# sx-wdec84-1_2.net
KiCad netlist of a schematic drawn in EAGLE
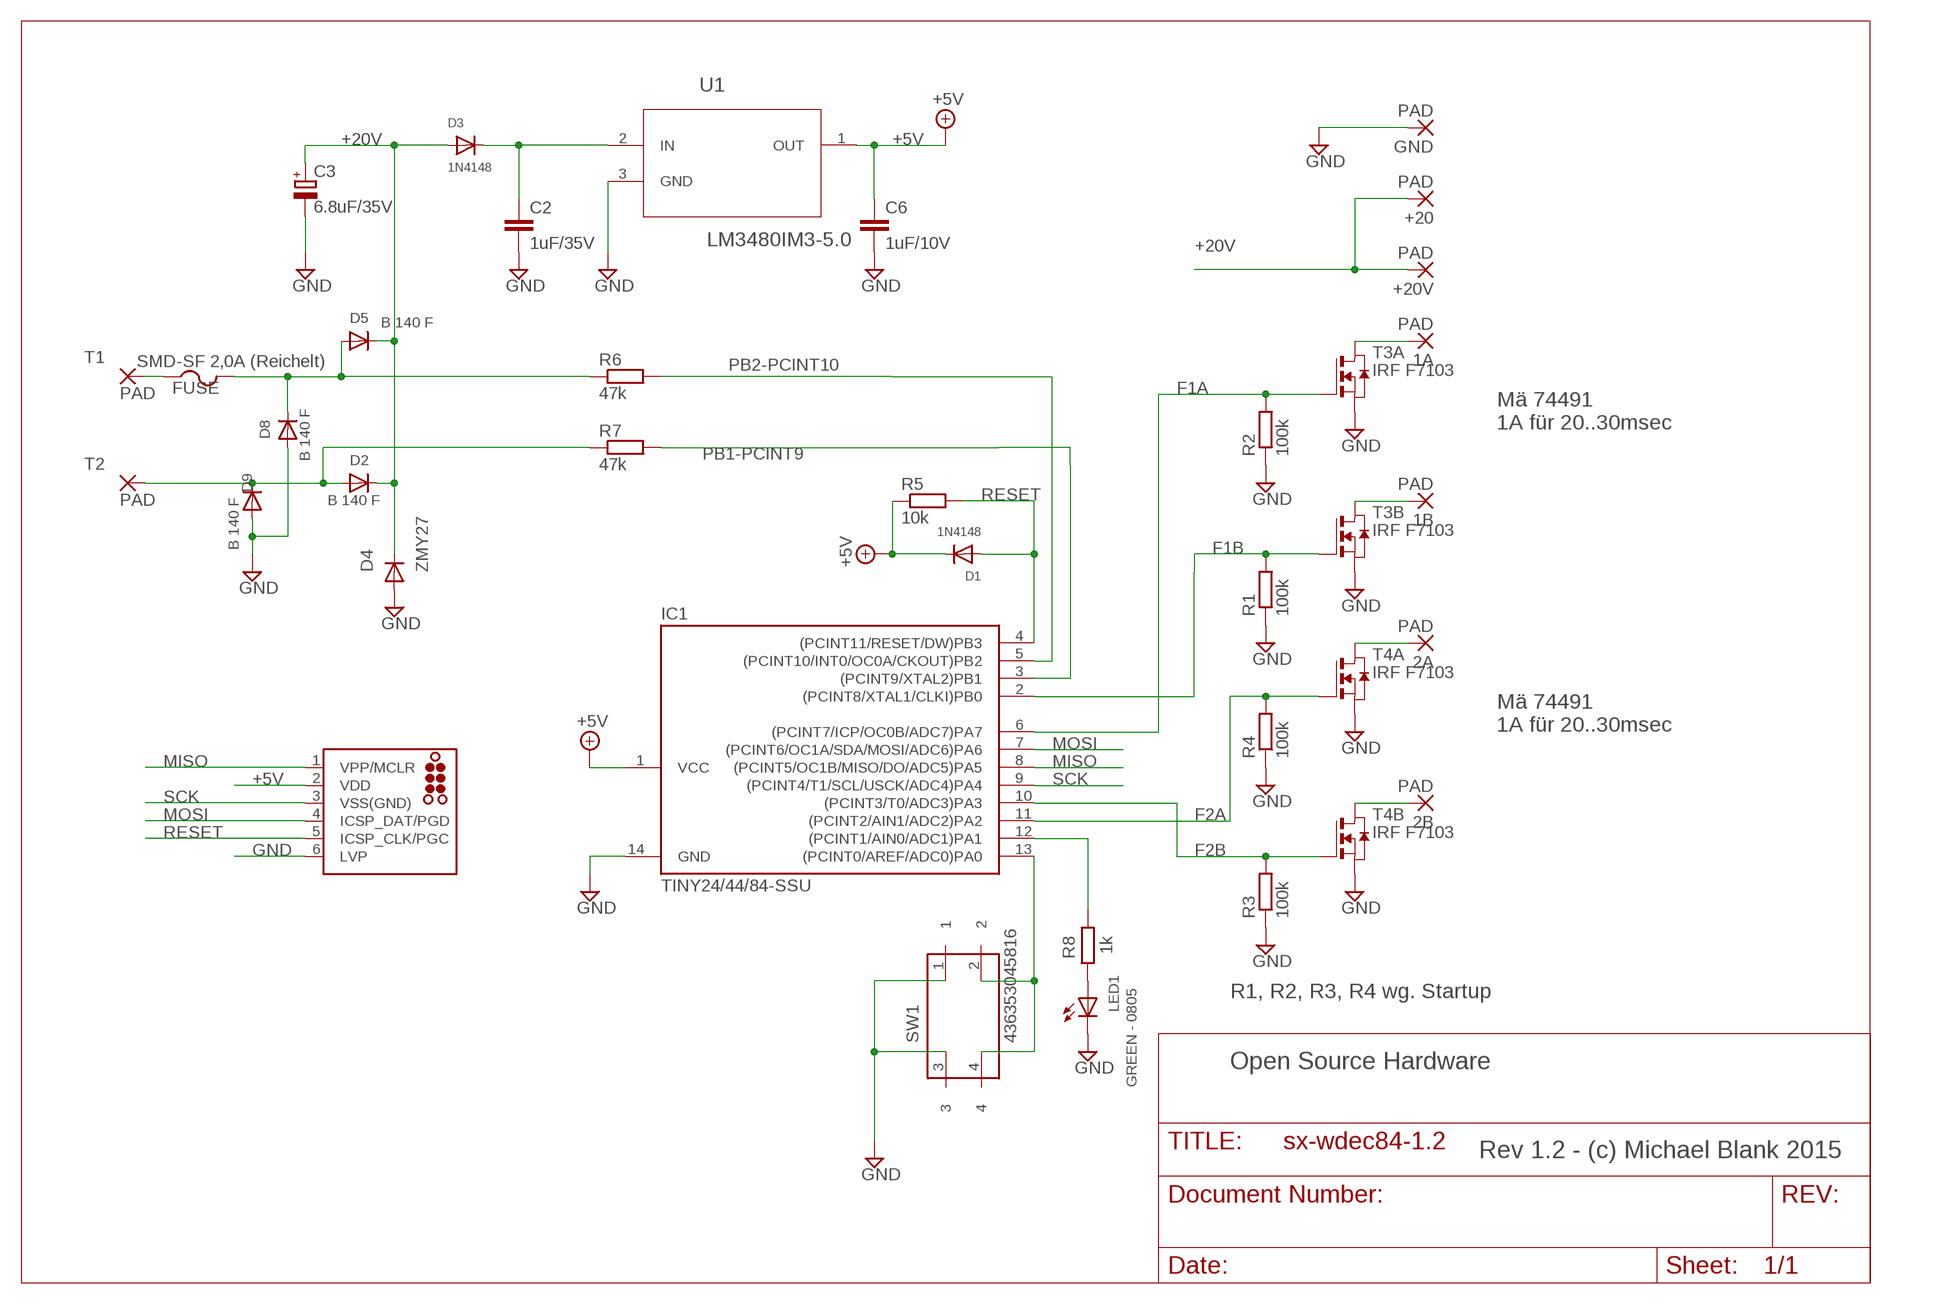
[diagram p0: schematic, sheet 1]

(export (version "E")
  (design (tool "Eeschema 10.0.6"))
  (components
    (comp (ref "+20")
      (value "PAD")
      (footprint "eagle-import:SMD1,27-2,54")
      (libsource (lib "eagle-import") (part "SMD2"))
    )
    (comp (ref "+20V")
      (value "PAD")
      (footprint "eagle-import:SMD1,27-2,54")
      (libsource (lib "eagle-import") (part "SMD2"))
    )
    (comp (ref "1A")
      (value "PAD")
      (footprint "eagle-import:SMD1,27-2,54")
      (libsource (lib "eagle-import") (part "SMD2"))
    )
    (comp (ref "1B")
      (value "PAD")
      (footprint "eagle-import:SMD1,27-2,54")
      (libsource (lib "eagle-import") (part "SMD2"))
    )
    (comp (ref "2A")
      (value "PAD")
      (footprint "eagle-import:SMD1,27-2,54")
      (libsource (lib "eagle-import") (part "SMD2"))
    )
    (comp (ref "2B")
      (value "PAD")
      (footprint "eagle-import:SMD1,27-2,54")
      (libsource (lib "eagle-import") (part "SMD2"))
    )
    (comp (ref "C2")
      (value "1uF/35V")
      (footprint "eagle-import:C0805")
      (libsource (lib "eagle-import") (part "C-EUC0805"))
    )
    (comp (ref "C3")
      (value "6.8uF/35V")
      (footprint "eagle-import:SMC_D")
      (libsource (lib "eagle-import") (part "CPOL-EUSMCD"))
    )
    (comp (ref "C6")
      (value "1uF/10V")
      (footprint "eagle-import:C0805")
      (libsource (lib "eagle-import") (part "C-EUC0805"))
    )
    (comp (ref "D1")
      (value "1N4148")
      (footprint "eagle-import:SOD-323F")
      (libsource (lib "eagle-import") (part "DIODESOD-323F"))
    )
    (comp (ref "D2")
      (value "B 140 F")
      (footprint "eagle-import:SMA-403D")
      (libsource (lib "eagle-import") (part "DIODESMA-403D"))
    )
    (comp (ref "D3")
      (value "1N4148")
      (footprint "eagle-import:SOD-323F")
      (libsource (lib "eagle-import") (part "DIODESOD-323F"))
    )
    (comp (ref "D4")
      (value "ZMY27")
      (footprint "eagle-import:MELF-MLL41")
      (libsource (lib "eagle-import") (part "DIODE-MELF-MLL41"))
    )
    (comp (ref "D5")
      (value "B 140 F")
      (footprint "eagle-import:SMA-403D")
      (libsource (lib "eagle-import") (part "DIODESMA-403D"))
    )
    (comp (ref "D8")
      (value "B 140 F")
      (footprint "eagle-import:SMA-403D")
      (libsource (lib "eagle-import") (part "DIODESMA-403D"))
    )
    (comp (ref "D9")
      (value "B 140 F")
      (footprint "eagle-import:SMA-403D")
      (libsource (lib "eagle-import") (part "DIODESMA-403D"))
    )
    (comp (ref "FUSE")
      (value "SMD-SF 2,0A (Reichelt)")
      (footprint "eagle-import:1812")
      (libsource (lib "eagle-import") (part "PTCFUSE-1812"))
    )
    (comp (ref "GND")
      (value "PAD")
      (footprint "eagle-import:SMD1,27-2,54")
      (libsource (lib "eagle-import") (part "SMD2"))
    )
    (comp (ref "IC1")
      (value "TINY24/44/84-SSU")
      (footprint "eagle-import:SOIC14")
      (libsource (lib "eagle-import") (part "TINY24/44/84-SSU"))
    )
    (comp (ref "J1")
      (value "ISP")
      (footprint "eagle-import:TC2030-MCP-NL")
      (libsource (lib "eagle-import") (part "TC2030-MCP-NL"))
    )
    (comp (ref "LED1")
      (value "GREEN - 0805")
      (footprint "eagle-import:LED-0805")
      (libsource (lib "eagle-import") (part "LED0805"))
    )
    (comp (ref "R1")
      (value "100k")
      (footprint "eagle-import:R0805W")
      (libsource (lib "eagle-import") (part "R-EU_R0805W"))
    )
    (comp (ref "R2")
      (value "100k")
      (footprint "eagle-import:R0805W")
      (libsource (lib "eagle-import") (part "R-EU_R0805W"))
    )
    (comp (ref "R3")
      (value "100k")
      (footprint "eagle-import:R0805W")
      (libsource (lib "eagle-import") (part "R-EU_R0805W"))
    )
    (comp (ref "R4")
      (value "100k")
      (footprint "eagle-import:R0805W")
      (libsource (lib "eagle-import") (part "R-EU_R0805W"))
    )
    (comp (ref "R5")
      (value "10k")
      (footprint "eagle-import:R0805W")
      (libsource (lib "eagle-import") (part "R-EU_R0805W"))
    )
    (comp (ref "R6")
      (value "47k")
      (footprint "eagle-import:R0805W")
      (libsource (lib "eagle-import") (part "R-EU_R0805W"))
    )
    (comp (ref "R7")
      (value "47k")
      (footprint "eagle-import:R0805W")
      (libsource (lib "eagle-import") (part "R-EU_R0805W"))
    )
    (comp (ref "R8")
      (value "1k")
      (footprint "eagle-import:R0805W")
      (libsource (lib "eagle-import") (part "R-EU_R0805W"))
    )
    (comp (ref "SW1")
      (value "436353045816")
      (footprint "eagle-import:436353045816")
      (libsource (lib "eagle-import") (part "436353045816"))
    )
    (comp (ref "T1")
      (value "PAD")
      (footprint "eagle-import:SMD1,27-2,54")
      (libsource (lib "eagle-import") (part "SMD2"))
    )
    (comp (ref "T2")
      (value "PAD")
      (footprint "eagle-import:SMD1,27-2,54")
      (libsource (lib "eagle-import") (part "SMD2"))
    )
    (comp (ref "T3")
      (value "IRF F7103")
      (footprint "eagle-import:SO8")
      (libsource (lib "eagle-import") (part "DMN3024LSD"))
    )
    (comp (ref "T4")
      (value "IRF F7103")
      (footprint "eagle-import:SO8")
      (libsource (lib "eagle-import") (part "DMN3024LSD"))
    )
    (comp (ref "U1")
      (value "LM3480IM3-5.0")
      (footprint "eagle-import:SOT95P263X110-3N")
      (fields (field (name "MPN") "LM3480IM3-50"))
      (libsource (lib "eagle-import") (part "LM3480IM3-5.0"))
    )
  )
  (nets
    (net (code "1") (name "+5V") (class "Default")
      (node (ref "C6") (pin "1") (pinfunction "1_1") (pintype "passive"))
      (node (ref "D1") (pin "C") (pinfunction "C_C") (pintype "passive"))
      (node (ref "IC1") (pin "1") (pinfunction "VCC_1") (pintype "power_in"))
      (node (ref "J1") (pin "2") (pinfunction "VDD_2") (pintype "power_in"))
      (node (ref "R5") (pin "1") (pinfunction "1_1") (pintype "passive"))
      (node (ref "U1") (pin "1") (pinfunction "OUT_1") (pintype "output"))
    )
    (net (code "2") (name "/+20V") (class "Default")
      (node (ref "+20") (pin "1") (pinfunction "P_1") (pintype "passive"))
      (node (ref "+20V") (pin "1") (pinfunction "P_1") (pintype "passive"))
      (node (ref "C3") (pin "+") (pinfunction "+_+") (pintype "passive"))
      (node (ref "D2") (pin "C") (pinfunction "C_C") (pintype "passive"))
      (node (ref "D3") (pin "A") (pinfunction "A_A") (pintype "passive"))
      (node (ref "D4") (pin "C") (pinfunction "C_C") (pintype "passive"))
      (node (ref "D5") (pin "C") (pinfunction "C_C") (pintype "passive"))
    )
    (net (code "3") (name "/F1A") (class "Default")
      (node (ref "IC1") (pin "6") (pinfunction "(PCINT7/ICP/OC0B/ADC7)PA7_6") (pintype "bidirectional"))
      (node (ref "R2") (pin "2") (pinfunction "2_2") (pintype "passive"))
      (node (ref "T3") (pin "2") (pinfunction "G_2") (pintype "passive"))
    )
    (net (code "4") (name "/F1B") (class "Default")
      (node (ref "IC1") (pin "2") (pinfunction "(PCINT8/XTAL1/CLKI)PB0_2") (pintype "bidirectional"))
      (node (ref "R1") (pin "2") (pinfunction "2_2") (pintype "passive"))
      (node (ref "T3") (pin "4") (pinfunction "G_4") (pintype "passive"))
    )
    (net (code "5") (name "/F2A") (class "Default")
      (node (ref "IC1") (pin "11") (pinfunction "(PCINT2/AIN1/ADC2)PA2_11") (pintype "bidirectional"))
      (node (ref "R4") (pin "2") (pinfunction "2_2") (pintype "passive"))
      (node (ref "T4") (pin "2") (pinfunction "G_2") (pintype "passive"))
    )
    (net (code "6") (name "/F2B") (class "Default")
      (node (ref "IC1") (pin "10") (pinfunction "(PCINT3/T0/ADC3)PA3_10") (pintype "bidirectional"))
      (node (ref "R3") (pin "2") (pinfunction "2_2") (pintype "passive"))
      (node (ref "T4") (pin "4") (pinfunction "G_4") (pintype "passive"))
    )
    (net (code "7") (name "/MISO") (class "Default")
      (node (ref "IC1") (pin "8") (pinfunction "(PCINT5/OC1B/MISO/DO/ADC5)PA5_8") (pintype "bidirectional"))
      (node (ref "J1") (pin "1") (pinfunction "VPP/MCLR_1") (pintype "passive"))
    )
    (net (code "8") (name "/MOSI") (class "Default")
      (node (ref "IC1") (pin "7") (pinfunction "(PCINT6/OC1A/SDA/MOSI/ADC6)PA6_7") (pintype "bidirectional"))
      (node (ref "J1") (pin "4") (pinfunction "ICSP_DAT/PGD_4") (pintype "bidirectional"))
    )
    (net (code "9") (name "/PB1-PCINT9") (class "Default")
      (node (ref "IC1") (pin "3") (pinfunction "(PCINT9/XTAL2)PB1_3") (pintype "bidirectional"))
      (node (ref "R7") (pin "2") (pinfunction "2_2") (pintype "passive"))
    )
    (net (code "10") (name "/PB2-PCINT10") (class "Default")
      (node (ref "IC1") (pin "5") (pinfunction "(PCINT10/INT0/OC0A/CKOUT)PB2_5") (pintype "bidirectional"))
      (node (ref "R6") (pin "2") (pinfunction "2_2") (pintype "passive"))
    )
    (net (code "11") (name "/RESET") (class "Default")
      (node (ref "D1") (pin "A") (pinfunction "A_A") (pintype "passive"))
      (node (ref "IC1") (pin "4") (pinfunction "(PCINT11/RESET/DW)PB3_4") (pintype "bidirectional"))
      (node (ref "J1") (pin "5") (pinfunction "ICSP_CLK/PGC_5") (pintype "output"))
      (node (ref "R5") (pin "2") (pinfunction "2_2") (pintype "passive"))
    )
    (net (code "12") (name "/SCK") (class "Default")
      (node (ref "IC1") (pin "9") (pinfunction "(PCINT4/T1/SCL/USCK/ADC4)PA4_9") (pintype "bidirectional"))
      (node (ref "J1") (pin "3") (pinfunction "VSS(GND)_3") (pintype "power_in"))
    )
    (net (code "13") (name "GND") (class "Default")
      (node (ref "C2") (pin "2") (pinfunction "2_2") (pintype "passive"))
      (node (ref "C3") (pin "-") (pinfunction "-_-") (pintype "passive"))
      (node (ref "C6") (pin "2") (pinfunction "2_2") (pintype "passive"))
      (node (ref "D4") (pin "A") (pinfunction "A_A") (pintype "passive"))
      (node (ref "D8") (pin "A") (pinfunction "A_A") (pintype "passive"))
      (node (ref "D9") (pin "A") (pinfunction "A_A") (pintype "passive"))
      (node (ref "GND") (pin "1") (pinfunction "P_1") (pintype "passive"))
      (node (ref "IC1") (pin "14") (pinfunction "GND_14") (pintype "power_in"))
      (node (ref "J1") (pin "6") (pinfunction "LVP_6") (pintype "bidirectional"))
      (node (ref "LED1") (pin "C") (pinfunction "C_C") (pintype "passive"))
      (node (ref "R1") (pin "1") (pinfunction "1_1") (pintype "passive"))
      (node (ref "R2") (pin "1") (pinfunction "1_1") (pintype "passive"))
      (node (ref "R3") (pin "1") (pinfunction "1_1") (pintype "passive"))
      (node (ref "R4") (pin "1") (pinfunction "1_1") (pintype "passive"))
      (node (ref "SW1") (pin "1") (pinfunction "1_1") (pintype "bidirectional"))
      (node (ref "SW1") (pin "3") (pinfunction "3_3") (pintype "bidirectional"))
      (node (ref "T3") (pin "1") (pinfunction "S_1") (pintype "passive"))
      (node (ref "T3") (pin "3") (pinfunction "S_3") (pintype "passive"))
      (node (ref "T4") (pin "1") (pinfunction "S_1") (pintype "passive"))
      (node (ref "T4") (pin "3") (pinfunction "S_3") (pintype "passive"))
      (node (ref "U1") (pin "3") (pinfunction "GND_3") (pintype "passive"))
    )
    (net (code "14") (name "Net-(1A-P)") (class "Default")
      (node (ref "1A") (pin "1") (pinfunction "P_1") (pintype "passive"))
      (node (ref "T3") (pin "7") (pinfunction "D_7") (pintype "passive"))
      (node (ref "T3") (pin "8") (pinfunction "D_8") (pintype "passive"))
    )
    (net (code "15") (name "Net-(1B-P)") (class "Default")
      (node (ref "1B") (pin "1") (pinfunction "P_1") (pintype "passive"))
      (node (ref "T3") (pin "5") (pinfunction "D_5") (pintype "passive"))
      (node (ref "T3") (pin "6") (pinfunction "D_6") (pintype "passive"))
    )
    (net (code "16") (name "Net-(2A-P)") (class "Default")
      (node (ref "2A") (pin "1") (pinfunction "P_1") (pintype "passive"))
      (node (ref "T4") (pin "7") (pinfunction "D_7") (pintype "passive"))
      (node (ref "T4") (pin "8") (pinfunction "D_8") (pintype "passive"))
    )
    (net (code "17") (name "Net-(2B-P)") (class "Default")
      (node (ref "2B") (pin "1") (pinfunction "P_1") (pintype "passive"))
      (node (ref "T4") (pin "5") (pinfunction "D_5") (pintype "passive"))
      (node (ref "T4") (pin "6") (pinfunction "D_6") (pintype "passive"))
    )
    (net (code "18") (name "Net-(D5-PadA)") (class "Default")
      (node (ref "D5") (pin "A") (pinfunction "A_A") (pintype "passive"))
      (node (ref "D8") (pin "C") (pinfunction "C_C") (pintype "passive"))
      (node (ref "FUSE") (pin "2") (pinfunction "2_2") (pintype "passive"))
      (node (ref "R6") (pin "1") (pinfunction "1_1") (pintype "passive"))
    )
    (net (code "19") (name "Net-(IC1-(PCINT0{slash}AREF{slash}ADC0)PA0)") (class "Default")
      (node (ref "IC1") (pin "13") (pinfunction "(PCINT0/AREF/ADC0)PA0_13") (pintype "bidirectional"))
      (node (ref "SW1") (pin "2") (pinfunction "2_2") (pintype "bidirectional"))
      (node (ref "SW1") (pin "4") (pinfunction "4_4") (pintype "bidirectional"))
    )
    (net (code "20") (name "Net-(IC1-(PCINT1{slash}AIN0{slash}ADC1)PA1)") (class "Default")
      (node (ref "IC1") (pin "12") (pinfunction "(PCINT1/AIN0/ADC1)PA1_12") (pintype "bidirectional"))
      (node (ref "R8") (pin "1") (pinfunction "1_1") (pintype "passive"))
    )
    (net (code "21") (name "Net-(LED1-PadA)") (class "Default")
      (node (ref "LED1") (pin "A") (pinfunction "A_A") (pintype "passive"))
      (node (ref "R8") (pin "2") (pinfunction "2_2") (pintype "passive"))
    )
    (net (code "22") (name "Net-(T1-P)") (class "Default")
      (node (ref "FUSE") (pin "1") (pinfunction "1_1") (pintype "passive"))
      (node (ref "T1") (pin "1") (pinfunction "P_1") (pintype "passive"))
    )
    (net (code "23") (name "Net-(T2-P)") (class "Default")
      (node (ref "D2") (pin "A") (pinfunction "A_A") (pintype "passive"))
      (node (ref "D9") (pin "C") (pinfunction "C_C") (pintype "passive"))
      (node (ref "R7") (pin "1") (pinfunction "1_1") (pintype "passive"))
      (node (ref "T2") (pin "1") (pinfunction "P_1") (pintype "passive"))
    )
    (net (code "24") (name "Net-(U1-IN)") (class "Default")
      (node (ref "C2") (pin "1") (pinfunction "1_1") (pintype "passive"))
      (node (ref "D3") (pin "C") (pinfunction "C_C") (pintype "passive"))
      (node (ref "U1") (pin "2") (pinfunction "IN_2") (pintype "power_in"))
    )
  )
)
